# BW1098OAK_LEFT_OV9282.net
KiCad netlist of a schematic drawn in Altium Designer
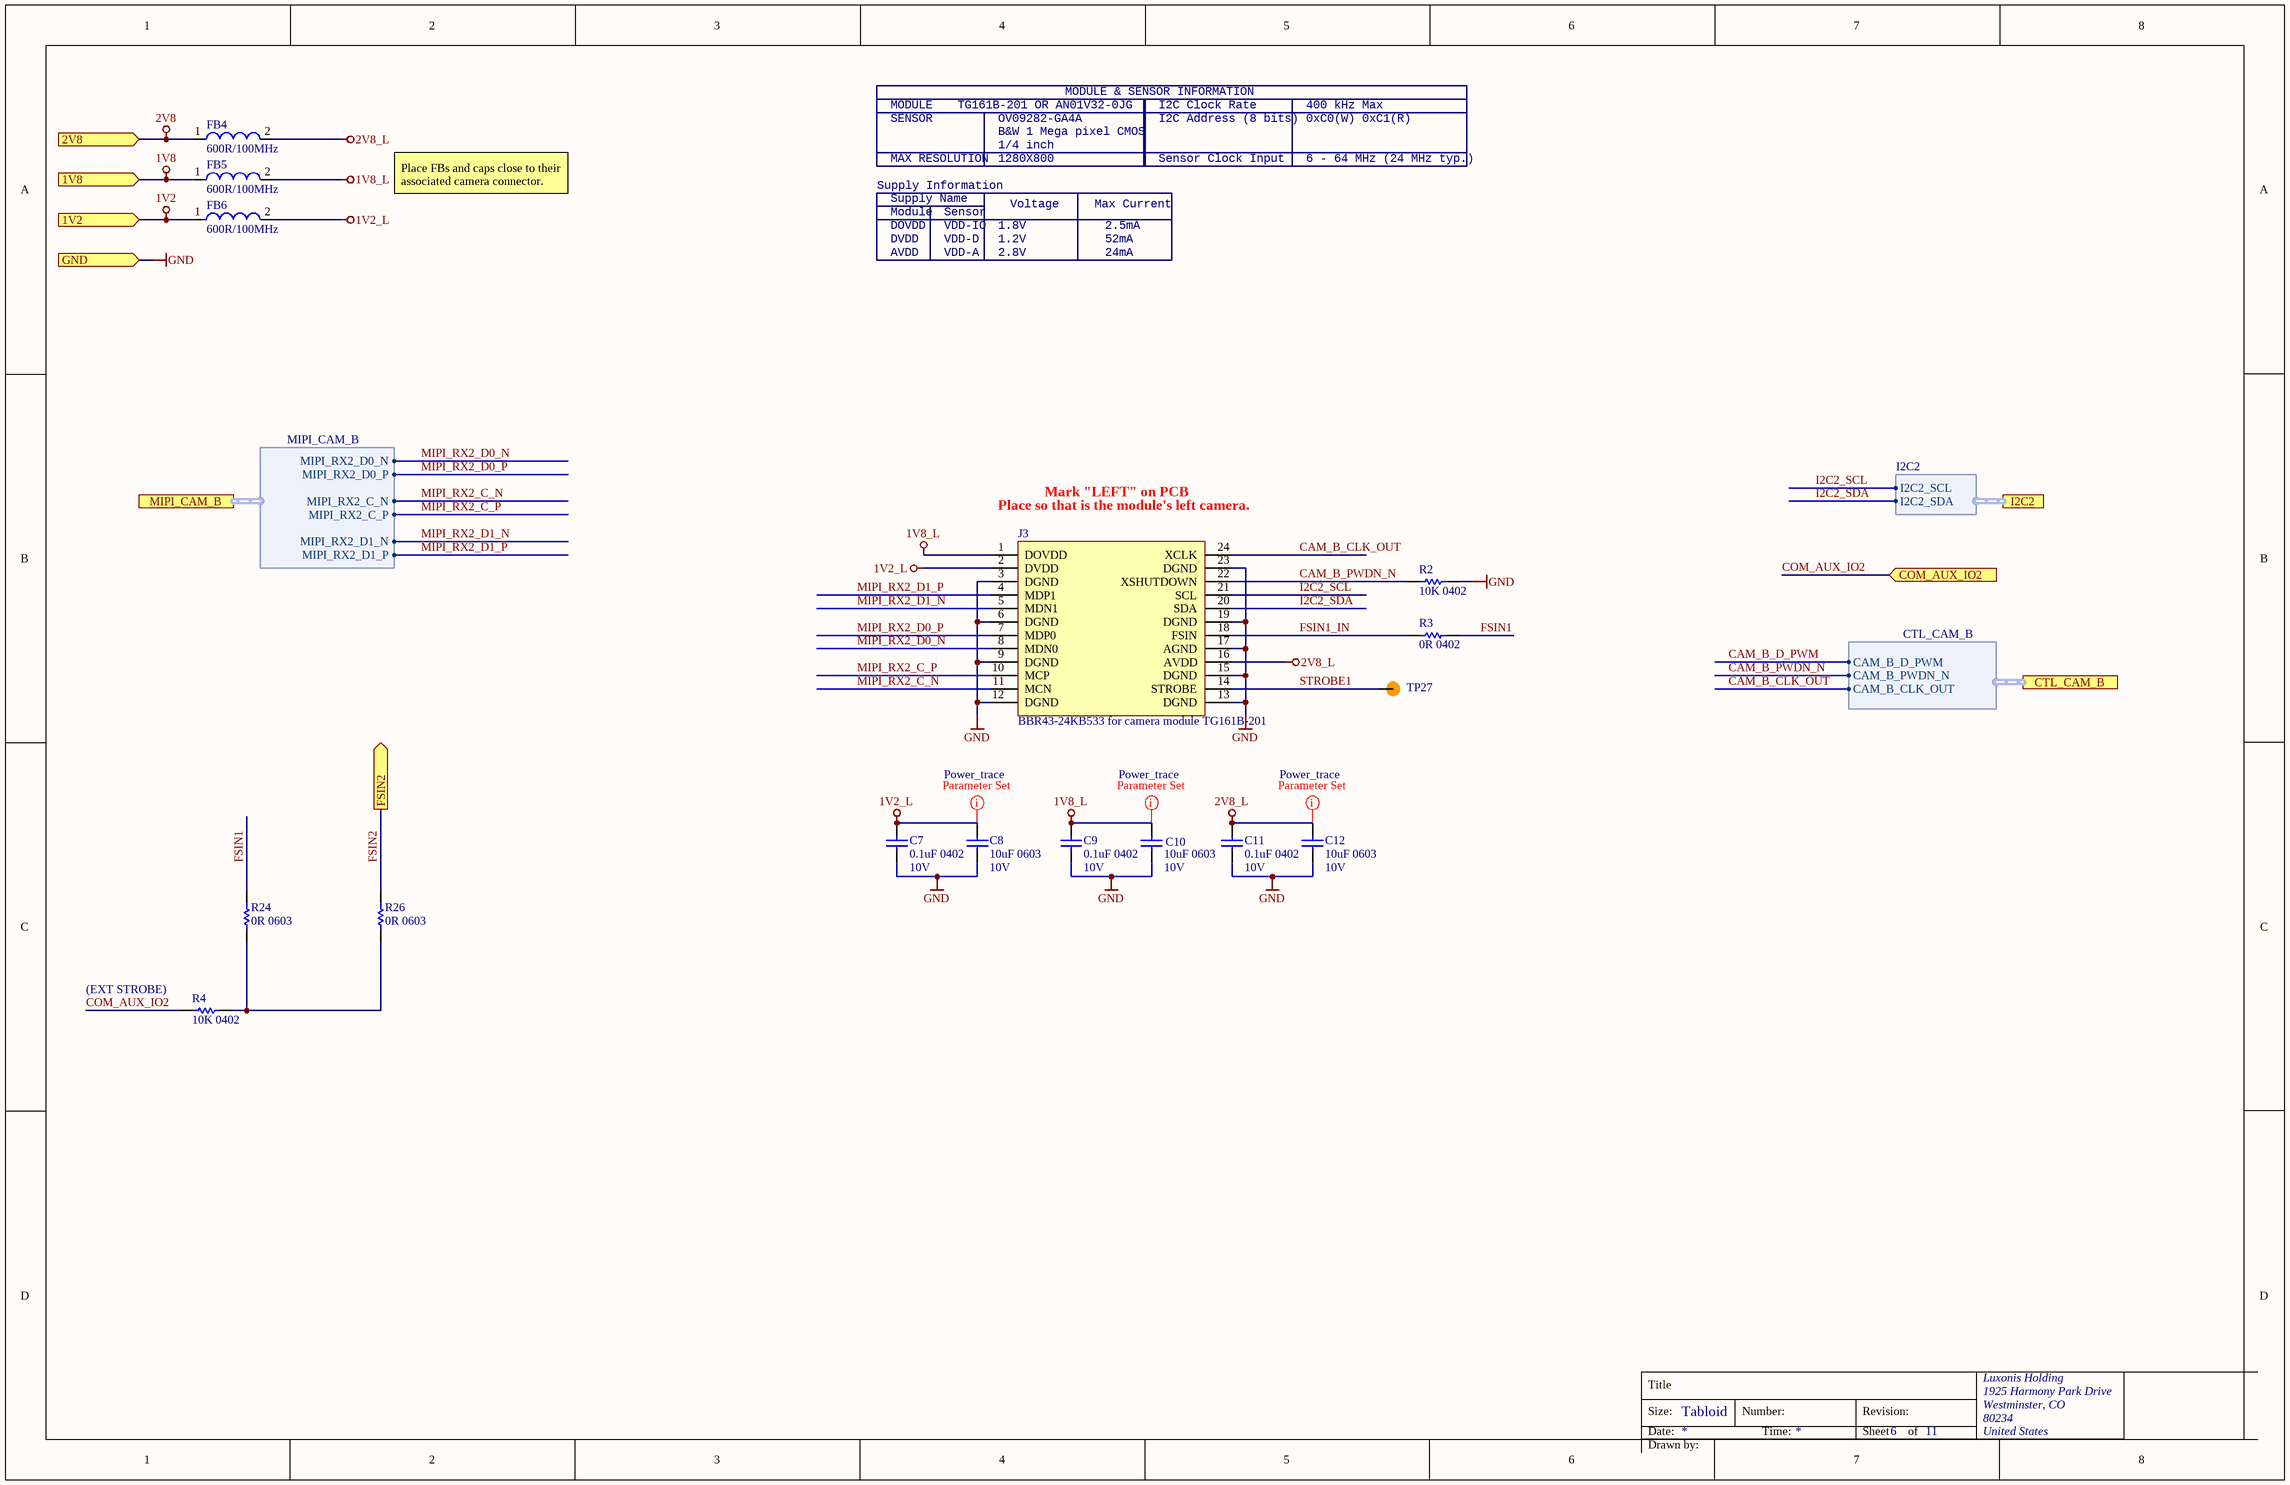
[diagram p0: BW1098OAK_LEFT_OV9282.SchDoc]

(export (version "E")
  (design (tool "Eeschema 10.0.6"))
  (components
    (comp (ref "C7")
      (value "0.1uF 0402")
      (footprint "CAP_Altium_Vault_Generic:CAPC0402(1005)70_L")
      (description "CAP CER 0.1UF 10V X7R 0402 5%")
      (fields (field (name "TOLERANCE") "5%") (field (name "VOLTAGE RATING") "10V"))
      (libsource (lib "LuxonisMaster") (part "GRM155R71A104JA01D"))
    )
    (comp (ref "C8")
      (value "10uF 0603")
      (footprint "CAP_Altium_Vault_Generic:CAPC0603(1608)100_L")
      (description "CAP CER 10UF 10V X5R 0603 20%")
      (fields (field (name "TOLERANCE") "20%") (field (name "VOLTAGE RATING") "10V"))
      (libsource (lib "LuxonisMaster") (part "GRM188R61A106ME69D"))
    )
    (comp (ref "C9")
      (value "0.1uF 0402")
      (footprint "CAP_Altium_Vault_Generic:CAPC0402(1005)70_L")
      (description "CAP CER 0.1UF 10V X7R 0402 5%")
      (fields (field (name "TOLERANCE") "5%") (field (name "VOLTAGE RATING") "10V"))
      (libsource (lib "LuxonisMaster") (part "GRM155R71A104JA01D"))
    )
    (comp (ref "C10")
      (value "10uF 0603")
      (footprint "CAP_Altium_Vault_Generic:CAPC0603(1608)100_L")
      (description "CAP CER 10UF 10V X5R 0603 20%")
      (fields (field (name "TOLERANCE") "20%") (field (name "VOLTAGE RATING") "10V"))
      (libsource (lib "LuxonisMaster") (part "GRM188R61A106ME69D"))
    )
    (comp (ref "C11")
      (value "0.1uF 0402")
      (footprint "CAP_Altium_Vault_Generic:CAPC0402(1005)70_L")
      (description "CAP CER 0.1UF 10V X7R 0402 5%")
      (fields (field (name "TOLERANCE") "5%") (field (name "VOLTAGE RATING") "10V"))
      (libsource (lib "LuxonisMaster") (part "GRM155R71A104JA01D"))
    )
    (comp (ref "C12")
      (value "10uF 0603")
      (footprint "CAP_Altium_Vault_Generic:CAPC0603(1608)100_L")
      (description "CAP CER 10UF 10V X5R 0603 20%")
      (fields (field (name "TOLERANCE") "20%") (field (name "VOLTAGE RATING") "10V"))
      (libsource (lib "LuxonisMaster") (part "GRM188R61A106ME69D"))
    )
    (comp (ref "FB4")
      (value "600R/100MHz")
      (footprint "LuxonisMaster:2508056017Y2")
      (description "FERRITE BEAD, 0.1OHM, 2A, 0805, 600R/100MHz")
      (fields (field (name "TOLERANCE") "25%"))
      (libsource (lib "LuxonisMaster") (part "2508056017Y2"))
    )
    (comp (ref "FB5")
      (value "600R/100MHz")
      (footprint "LuxonisMaster:2508056017Y2")
      (description "FERRITE BEAD, 0.1OHM, 2A, 0805, 600R/100MHz")
      (fields (field (name "TOLERANCE") "25%"))
      (libsource (lib "LuxonisMaster") (part "2508056017Y2"))
    )
    (comp (ref "FB6")
      (value "600R/100MHz")
      (footprint "LuxonisMaster:2508056017Y2")
      (description "FERRITE BEAD, 0.1OHM, 2A, 0805, 600R/100MHz")
      (fields (field (name "TOLERANCE") "25%"))
      (libsource (lib "LuxonisMaster") (part "2508056017Y2"))
    )
    (comp (ref "J3")
      (value "BBR43-24KB533 for camera module TG161B-201")
      (footprint "LuxonisMaster:TG161B-201 / AN01V32 - Board Wrap (7mm setback) MinPads")
      (description "CONN 24 way, 2 row board to board connector SMD")
      (libsource (lib "LuxonisMaster") (part "TG161B-201_Connector"))
    )
    (comp (ref "R2")
      (value "10K 0402")
      (footprint "RES_Altium_Vault_Generic:RESC0402(1005)_L")
      (fields (field (name "TOLERANCE") "1%"))
      (libsource (lib "LuxonisMaster") (part "RC0402FR-1310KL"))
    )
    (comp (ref "R3")
      (value "0R 0402")
      (footprint "RES_Altium_Vault_Generic:RESC0402(1005)_L")
      (description "RES SMD 0 OHM JUMPER 1/16W 0402")
      (fields (field (name "TOLERANCE") "5%"))
      (libsource (lib "LuxonisMaster") (part "CRCW04020000Z0ED"))
    )
    (comp (ref "R4")
      (value "10K 0402")
      (footprint "RES_Altium_Vault_Generic:RESC0402(1005)_L")
      (fields (field (name "TOLERANCE") "1%"))
      (libsource (lib "LuxonisMaster") (part "RC0402FR-1310KL"))
    )
    (comp (ref "R24")
      (value "0R 0603")
      (footprint "RES_Altium_Vault_Generic:RESC0603(1608)_N")
      (fields (field (name "TOLERANCE") "5%"))
      (libsource (lib "LuxonisMaster") (part "CRCW06030000Z0EA"))
    )
    (comp (ref "R26")
      (value "0R 0603")
      (footprint "RES_Altium_Vault_Generic:RESC0603(1608)_N")
      (fields (field (name "TOLERANCE") "5%"))
      (libsource (lib "LuxonisMaster") (part "CRCW06030000Z0EA"))
    )
    (comp (ref "TP27")
      (value "TP100_200_NS")
      (footprint "LuxonisMaster:TP100_200_NS")
      (libsource (lib "LuxonisMaster") (part "TEST_POINT"))
    )
  )
  (nets
    (net (code "4") (name "/CAM_B_CLK_OUT") (class "Default")
      (node (ref "J3") (pin "24") (pinfunction "XCLK_24") (pintype "passive"))
    )
    (net (code "6") (name "/CAM_B_PWDN_N") (class "Default")
      (node (ref "J3") (pin "22") (pinfunction "XSHUTDOWN_22") (pintype "passive"))
      (node (ref "R2") (pin "1") (pinfunction "1_1") (pintype "passive"))
    )
    (net (code "7") (name "/COM_AUX_IO2") (class "Default")
      (node (ref "R4") (pin "1") (pinfunction "1_1") (pintype "passive"))
    )
    (net (code "8") (name "/FSIN1") (class "Default")
      (node (ref "R24") (pin "2") (pinfunction "2_2") (pintype "passive"))
      (node (ref "R3") (pin "2") (pinfunction "2_2") (pintype "passive"))
    )
    (net (code "9") (name "/FSIN1_IN") (class "Default")
      (node (ref "J3") (pin "18") (pinfunction "FSIN_18") (pintype "passive"))
      (node (ref "R3") (pin "1") (pinfunction "1_1") (pintype "passive"))
    )
    (net (code "10") (name "/FSIN2") (class "Default")
      (node (ref "R26") (pin "2") (pinfunction "2_2") (pintype "passive"))
    )
    (net (code "11") (name "/I2C2_SCL") (class "Default")
      (node (ref "J3") (pin "21") (pinfunction "SCL_21") (pintype "passive"))
    )
    (net (code "12") (name "/I2C2_SDA") (class "Default")
      (node (ref "J3") (pin "20") (pinfunction "SDA_20") (pintype "passive"))
    )
    (net (code "13") (name "/MIPI_RX2_C_N") (class "Default")
      (node (ref "J3") (pin "11") (pinfunction "MCN_11") (pintype "passive"))
    )
    (net (code "14") (name "/MIPI_RX2_C_P") (class "Default")
      (node (ref "J3") (pin "10") (pinfunction "MCP_10") (pintype "passive"))
    )
    (net (code "15") (name "/MIPI_RX2_D0_N") (class "Default")
      (node (ref "J3") (pin "8") (pinfunction "MDN0_8") (pintype "passive"))
    )
    (net (code "16") (name "/MIPI_RX2_D0_P") (class "Default")
      (node (ref "J3") (pin "7") (pinfunction "MDP0_7") (pintype "passive"))
    )
    (net (code "17") (name "/MIPI_RX2_D1_N") (class "Default")
      (node (ref "J3") (pin "5") (pinfunction "MDN1_5") (pintype "passive"))
    )
    (net (code "18") (name "/MIPI_RX2_D1_P") (class "Default")
      (node (ref "J3") (pin "4") (pinfunction "MDP1_4") (pintype "passive"))
    )
    (net (code "19") (name "/STROBE1") (class "Default")
      (node (ref "J3") (pin "14") (pinfunction "STROBE_14") (pintype "passive"))
      (node (ref "TP27") (pin "1") (pintype "passive"))
    )
    (net (code "23") (name "1V2") (class "Default")
      (node (ref "FB6") (pin "1") (pinfunction "1_1") (pintype "passive"))
    )
    (net (code "24") (name "1V2_L") (class "Default")
      (node (ref "C7") (pin "2") (pinfunction "2_2") (pintype "passive"))
      (node (ref "C8") (pin "2") (pinfunction "2_2") (pintype "passive"))
      (node (ref "FB6") (pin "2") (pinfunction "2_2") (pintype "passive"))
      (node (ref "J3") (pin "2") (pinfunction "DVDD_2") (pintype "passive"))
    )
    (net (code "25") (name "1V8") (class "Default")
      (node (ref "FB5") (pin "1") (pinfunction "1_1") (pintype "passive"))
    )
    (net (code "26") (name "1V8_L") (class "Default")
      (node (ref "C10") (pin "2") (pinfunction "2_2") (pintype "passive"))
      (node (ref "C9") (pin "2") (pinfunction "2_2") (pintype "passive"))
      (node (ref "FB5") (pin "2") (pinfunction "2_2") (pintype "passive"))
      (node (ref "J3") (pin "1") (pinfunction "DOVDD_1") (pintype "passive"))
    )
    (net (code "27") (name "2V8") (class "Default")
      (node (ref "FB4") (pin "1") (pinfunction "1_1") (pintype "passive"))
    )
    (net (code "28") (name "2V8_L") (class "Default")
      (node (ref "C11") (pin "2") (pinfunction "2_2") (pintype "passive"))
      (node (ref "C12") (pin "2") (pinfunction "2_2") (pintype "passive"))
      (node (ref "FB4") (pin "2") (pinfunction "2_2") (pintype "passive"))
      (node (ref "J3") (pin "16") (pinfunction "AVDD_16") (pintype "passive"))
    )
    (net (code "29") (name "GND") (class "Default")
      (node (ref "C10") (pin "1") (pinfunction "1_1") (pintype "passive"))
      (node (ref "C11") (pin "1") (pinfunction "1_1") (pintype "passive"))
      (node (ref "C12") (pin "1") (pinfunction "1_1") (pintype "passive"))
      (node (ref "C7") (pin "1") (pinfunction "1_1") (pintype "passive"))
      (node (ref "C8") (pin "1") (pinfunction "1_1") (pintype "passive"))
      (node (ref "C9") (pin "1") (pinfunction "1_1") (pintype "passive"))
      (node (ref "J3") (pin "12") (pinfunction "DGND_12") (pintype "passive"))
      (node (ref "J3") (pin "13") (pinfunction "DGND_13") (pintype "passive"))
      (node (ref "J3") (pin "15") (pinfunction "DGND_15") (pintype "passive"))
      (node (ref "J3") (pin "17") (pinfunction "AGND_17") (pintype "passive"))
      (node (ref "J3") (pin "19") (pinfunction "DGND_19") (pintype "passive"))
      (node (ref "J3") (pin "23") (pinfunction "DGND_23") (pintype "passive"))
      (node (ref "J3") (pin "3") (pinfunction "DGND_3") (pintype "passive"))
      (node (ref "J3") (pin "6") (pinfunction "DGND_6") (pintype "passive"))
      (node (ref "J3") (pin "9") (pinfunction "DGND_9") (pintype "passive"))
      (node (ref "R2") (pin "2") (pinfunction "2_2") (pintype "passive"))
    )
    (net (code "30") (name "Net-(R24-Pad1)") (class "Default")
      (node (ref "R24") (pin "1") (pinfunction "1_1") (pintype "passive"))
      (node (ref "R26") (pin "1") (pinfunction "1_1") (pintype "passive"))
      (node (ref "R4") (pin "2") (pinfunction "2_2") (pintype "passive"))
    )
  )
)
